# rpmsens.net
KiCad netlist of a schematic drawn in Altium Designer
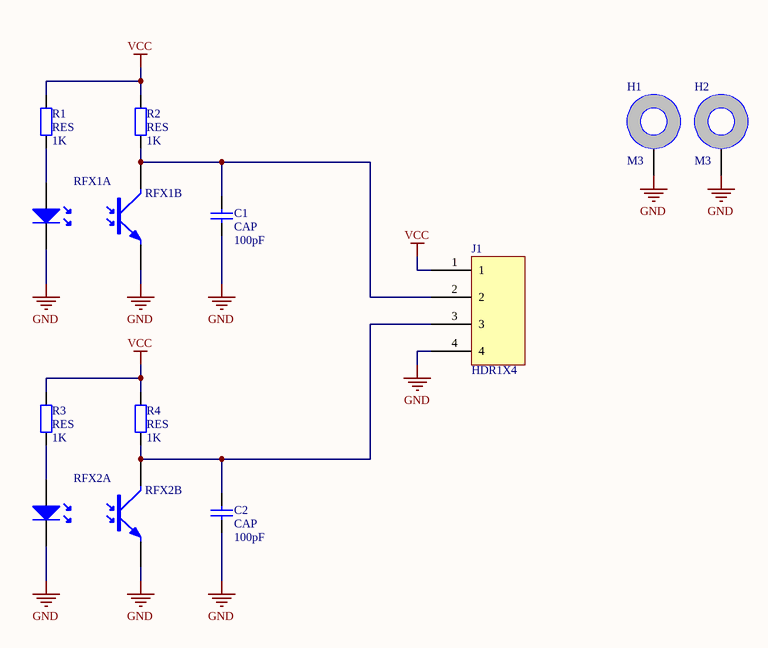
[diagram p0: rpmsens.SchDoc]

(export (version "E")
  (design (tool "Eeschema 10.0.6"))
  (components
    (comp (ref "C1")
      (value "CAP")
      (footprint "CAPC1608X08M")
      (description "Capacitor")
      (fields (field (name "ALTIUM_VALUE") "100pF") (field (name "PUBLISHER") "Altium Limited"))
      (libsource (lib "std") (part "CAP"))
    )
    (comp (ref "C2")
      (value "CAP")
      (footprint "CAPC1608X08M")
      (description "Capacitor")
      (fields (field (name "ALTIUM_VALUE") "100pF") (field (name "PUBLISHER") "Altium Limited"))
      (libsource (lib "std") (part "CAP"))
    )
    (comp (ref "H1") (value "M3") (footprint "MOUNT_M3") (libsource (lib "std") (part "MOUNT_M3")))
    (comp (ref "H2") (value "M3") (footprint "MOUNT_M3") (libsource (lib "std") (part "MOUNT_M3")))
    (comp (ref "J1")
      (value "HDR1X4")
      (footprint "HEADER_1X4")
      (description "4pin header")
      (libsource (lib "std") (part "HDR1X4"))
    )
    (comp (ref "R1")
      (value "RES")
      (footprint "RESC1608X06M")
      (description "Resistor")
      (fields (field (name "ALTIUM_VALUE") "1K") (field (name "PUBLISHER") "Altium Limited"))
      (libsource (lib "std") (part "RES"))
    )
    (comp (ref "R2")
      (value "RES")
      (footprint "RESC1608X06M")
      (description "Resistor")
      (fields (field (name "ALTIUM_VALUE") "1K") (field (name "PUBLISHER") "Altium Limited"))
      (libsource (lib "std") (part "RES"))
    )
    (comp (ref "R3")
      (value "RES")
      (footprint "RESC1608X06M")
      (description "Resistor")
      (fields (field (name "ALTIUM_VALUE") "1K") (field (name "PUBLISHER") "Altium Limited"))
      (libsource (lib "std") (part "RES"))
    )
    (comp (ref "R4")
      (value "RES")
      (footprint "RESC1608X06M")
      (description "Resistor")
      (fields (field (name "ALTIUM_VALUE") "1K") (field (name "PUBLISHER") "Altium Limited"))
      (libsource (lib "std") (part "RES"))
    )
    (comp (ref "RFX1")
      (value "~")
      (footprint "RFX4")
      (description "SMT Reflective Object Sensor")
      (libsource (lib "std") (part "QRE113GR"))
    )
    (comp (ref "RFX2")
      (value "~")
      (footprint "RFX4")
      (description "SMT Reflective Object Sensor")
      (libsource (lib "std") (part "QRE113GR"))
    )
  )
  (nets
    (net (code "1") (name "GND") (class "Default")
      (node (ref "C1") (pin "1") (pinfunction "1_1") (pintype "passive"))
      (node (ref "C2") (pin "1") (pinfunction "1_1") (pintype "passive"))
      (node (ref "H1") (pin "1") (pinfunction "1_1") (pintype "passive"))
      (node (ref "H2") (pin "1") (pinfunction "1_1") (pintype "passive"))
      (node (ref "J1") (pin "4") (pinfunction "4_4") (pintype "passive"))
      (node (ref "RFX1") (pin "2") (pinfunction "K_2") (pintype "passive"))
      (node (ref "RFX1") (pin "4") (pinfunction "E_4") (pintype "passive"))
      (node (ref "RFX2") (pin "2") (pinfunction "K_2") (pintype "passive"))
      (node (ref "RFX2") (pin "4") (pinfunction "E_4") (pintype "passive"))
    )
    (net (code "2") (name "Net-(RFX1A-A)") (class "Default")
      (node (ref "R1") (pin "1") (pinfunction "1_1") (pintype "passive"))
      (node (ref "RFX1") (pin "1") (pinfunction "A_1") (pintype "passive"))
    )
    (net (code "3") (name "Net-(RFX1B-C)") (class "Default")
      (node (ref "C1") (pin "2") (pinfunction "2_2") (pintype "passive"))
      (node (ref "J1") (pin "2") (pinfunction "2_2") (pintype "passive"))
      (node (ref "R2") (pin "1") (pinfunction "1_1") (pintype "passive"))
      (node (ref "RFX1") (pin "3") (pinfunction "C_3") (pintype "passive"))
    )
    (net (code "4") (name "Net-(RFX2A-A)") (class "Default")
      (node (ref "R3") (pin "1") (pinfunction "1_1") (pintype "passive"))
      (node (ref "RFX2") (pin "1") (pinfunction "A_1") (pintype "passive"))
    )
    (net (code "5") (name "Net-(RFX2B-C)") (class "Default")
      (node (ref "C2") (pin "2") (pinfunction "2_2") (pintype "passive"))
      (node (ref "J1") (pin "3") (pinfunction "3_3") (pintype "passive"))
      (node (ref "R4") (pin "1") (pinfunction "1_1") (pintype "passive"))
      (node (ref "RFX2") (pin "3") (pinfunction "C_3") (pintype "passive"))
    )
    (net (code "6") (name "VCC") (class "Default")
      (node (ref "J1") (pin "1") (pinfunction "1_1") (pintype "passive"))
      (node (ref "R1") (pin "2") (pinfunction "2_2") (pintype "passive"))
      (node (ref "R2") (pin "2") (pinfunction "2_2") (pintype "passive"))
      (node (ref "R3") (pin "2") (pinfunction "2_2") (pintype "passive"))
      (node (ref "R4") (pin "2") (pinfunction "2_2") (pintype "passive"))
    )
  )
)
